# Bistable_Multivibrator.net
KiCad netlist of a schematic drawn in EAGLE
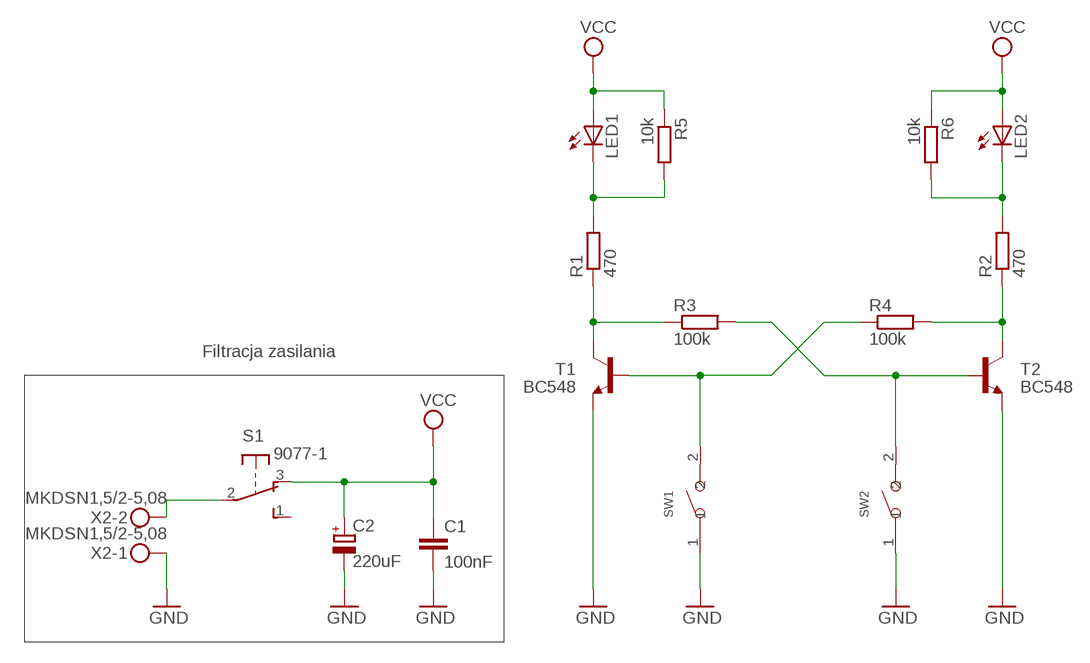
[diagram p0: schematic, sheet 1]

(export (version "E")
  (design (tool "Eeschema 10.0.6"))
  (components
    (comp (ref "C1")
      (value "100nF")
      (footprint "eagle-import:C025-024X044")
      (libsource (lib "eagle-import") (part "C-EU025-024X044"))
    )
    (comp (ref "C2")
      (value "220uF")
      (footprint "eagle-import:E3,5-8")
      (libsource (lib "eagle-import") (part "CPOL-EUE3.5-8"))
    )
    (comp (ref "LED1")
      (value "LED5MM")
      (footprint "eagle-import:LED5MM")
      (libsource (lib "eagle-import") (part "LED5MM"))
    )
    (comp (ref "LED2")
      (value "LED5MM")
      (footprint "eagle-import:LED5MM")
      (libsource (lib "eagle-import") (part "LED5MM"))
    )
    (comp (ref "R1")
      (value "470")
      (footprint "eagle-import:0204_7")
      (libsource (lib "eagle-import") (part "R-EU_0204/7"))
    )
    (comp (ref "R2")
      (value "470")
      (footprint "eagle-import:0204_7")
      (libsource (lib "eagle-import") (part "R-EU_0204/7"))
    )
    (comp (ref "R3")
      (value "100k")
      (footprint "eagle-import:0204_7")
      (libsource (lib "eagle-import") (part "R-EU_0204/7"))
    )
    (comp (ref "R4")
      (value "100k")
      (footprint "eagle-import:0204_7")
      (libsource (lib "eagle-import") (part "R-EU_0204/7"))
    )
    (comp (ref "R5")
      (value "10k")
      (footprint "eagle-import:0204_7")
      (libsource (lib "eagle-import") (part "R-EU_0204/7"))
    )
    (comp (ref "R6")
      (value "10k")
      (footprint "eagle-import:0204_7")
      (libsource (lib "eagle-import") (part "R-EU_0204/7"))
    )
    (comp (ref "S1")
      (value "9077-1")
      (footprint "eagle-import:9077-1")
      (libsource (lib "eagle-import") (part "9077-1"))
    )
    (comp (ref "SW1")
      (value "DIP-BUTTON(2P-6.0X3.0X4.3MM)-TS-1101F")
      (footprint "eagle-import:SW2-5.0-6.0X3.0X4.3MM")
      (libsource (lib "eagle-import") (part "DIP-BUTTON(2P-6.0X3.0X4.3MM)-TS-1101F"))
    )
    (comp (ref "SW2")
      (value "DIP-BUTTON(2P-6.0X3.0X4.3MM)-TS-1101F")
      (footprint "eagle-import:SW2-5.0-6.0X3.0X4.3MM")
      (libsource (lib "eagle-import") (part "DIP-BUTTON(2P-6.0X3.0X4.3MM)-TS-1101F"))
    )
    (comp (ref "T1")
      (value "BC548")
      (footprint "eagle-import:TO92-CBE")
      (libsource (lib "eagle-import") (part "-NPN-TO92-CBEBC547B"))
    )
    (comp (ref "T2")
      (value "BC548")
      (footprint "eagle-import:TO92-CBE")
      (libsource (lib "eagle-import") (part "-NPN-TO92-CBEBC547B"))
    )
    (comp (ref "X2")
      (value "MKDSN1,5/2-5,08")
      (footprint "eagle-import:MKDSN1,5_2-5,08")
      (libsource (lib "eagle-import") (part "MKDSN1,5/2-5,08"))
    )
  )
  (nets
    (net (code "1") (name "GND") (class "Default")
      (node (ref "C1") (pin "2") (pinfunction "2_2") (pintype "passive"))
      (node (ref "C2") (pin "-") (pinfunction "-_-") (pintype "passive"))
      (node (ref "SW1") (pin "1") (pinfunction "1_1") (pintype "bidirectional"))
      (node (ref "SW2") (pin "1") (pinfunction "1_1") (pintype "bidirectional"))
      (node (ref "T1") (pin "E") (pinfunction "E_E") (pintype "passive"))
      (node (ref "T2") (pin "E") (pinfunction "E_E") (pintype "passive"))
      (node (ref "X2") (pin "1") (pinfunction "KL_1") (pintype "passive"))
    )
    (net (code "2") (name "Net-(LED1-C)") (class "Default")
      (node (ref "LED1") (pin "K") (pinfunction "C_K") (pintype "passive"))
      (node (ref "R1") (pin "2") (pinfunction "2_2") (pintype "passive"))
      (node (ref "R5") (pin "2") (pinfunction "2_2") (pintype "passive"))
    )
    (net (code "3") (name "Net-(LED2-C)") (class "Default")
      (node (ref "LED2") (pin "K") (pinfunction "C_K") (pintype "passive"))
      (node (ref "R2") (pin "2") (pinfunction "2_2") (pintype "passive"))
      (node (ref "R6") (pin "2") (pinfunction "2_2") (pintype "passive"))
    )
    (net (code "4") (name "Net-(R1-Pad1)") (class "Default")
      (node (ref "R1") (pin "1") (pinfunction "1_1") (pintype "passive"))
      (node (ref "R3") (pin "1") (pinfunction "1_1") (pintype "passive"))
      (node (ref "T1") (pin "C") (pinfunction "C_C") (pintype "passive"))
    )
    (net (code "5") (name "Net-(R2-Pad1)") (class "Default")
      (node (ref "R2") (pin "1") (pinfunction "1_1") (pintype "passive"))
      (node (ref "R4") (pin "2") (pinfunction "2_2") (pintype "passive"))
      (node (ref "T2") (pin "C") (pinfunction "C_C") (pintype "passive"))
    )
    (net (code "6") (name "Net-(R3-Pad2)") (class "Default")
      (node (ref "R3") (pin "2") (pinfunction "2_2") (pintype "passive"))
      (node (ref "SW2") (pin "2") (pinfunction "2_2") (pintype "bidirectional"))
      (node (ref "T2") (pin "B") (pinfunction "B_B") (pintype "passive"))
    )
    (net (code "7") (name "Net-(R4-Pad1)") (class "Default")
      (node (ref "R4") (pin "1") (pinfunction "1_1") (pintype "passive"))
      (node (ref "SW1") (pin "2") (pinfunction "2_2") (pintype "bidirectional"))
      (node (ref "T1") (pin "B") (pinfunction "B_B") (pintype "passive"))
    )
    (net (code "8") (name "Net-(S1-P)") (class "Default")
      (node (ref "S1") (pin "2") (pinfunction "P_2") (pintype "passive"))
      (node (ref "X2") (pin "2") (pinfunction "KL_2") (pintype "passive"))
    )
    (net (code "9") (name "VCC") (class "Default")
      (node (ref "C1") (pin "1") (pinfunction "1_1") (pintype "passive"))
      (node (ref "C2") (pin "+") (pinfunction "+_+") (pintype "passive"))
      (node (ref "LED1") (pin "A") (pinfunction "A_A") (pintype "passive"))
      (node (ref "LED2") (pin "A") (pinfunction "A_A") (pintype "passive"))
      (node (ref "R5") (pin "1") (pinfunction "1_1") (pintype "passive"))
      (node (ref "R6") (pin "1") (pinfunction "1_1") (pintype "passive"))
      (node (ref "S1") (pin "3") (pinfunction "O_3") (pintype "passive"))
    )
    (net (code "10") (name "unconnected-(S1-S-Pad1)") (class "Default")
      (node (ref "S1") (pin "1") (pinfunction "S_1") (pintype "passive"))
    )
  )
)
